# WheelDriver_RevC_newlayoutfinal.net
KiCad netlist of a schematic drawn in EAGLE
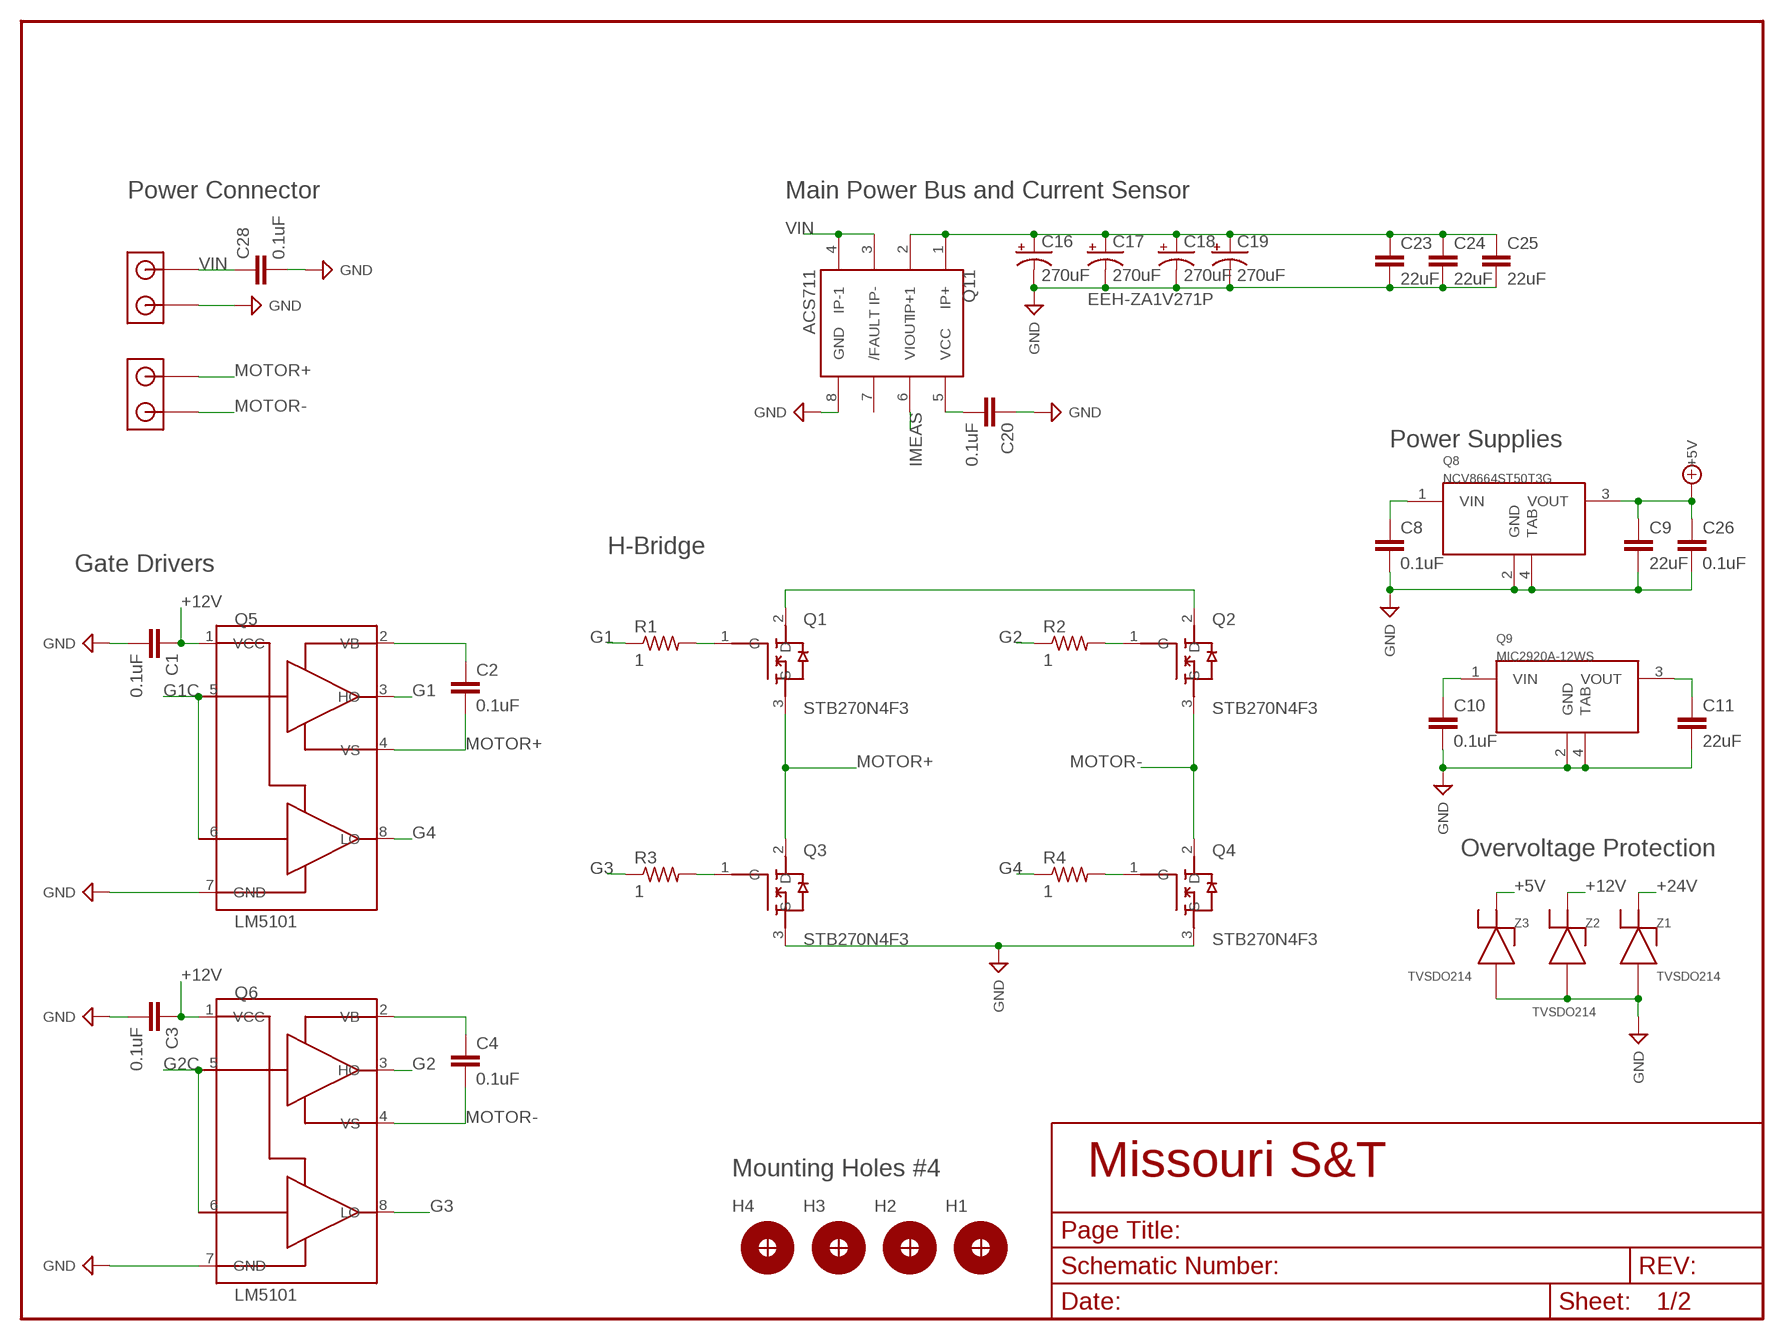
[diagram p0: schematic, sheet 1]
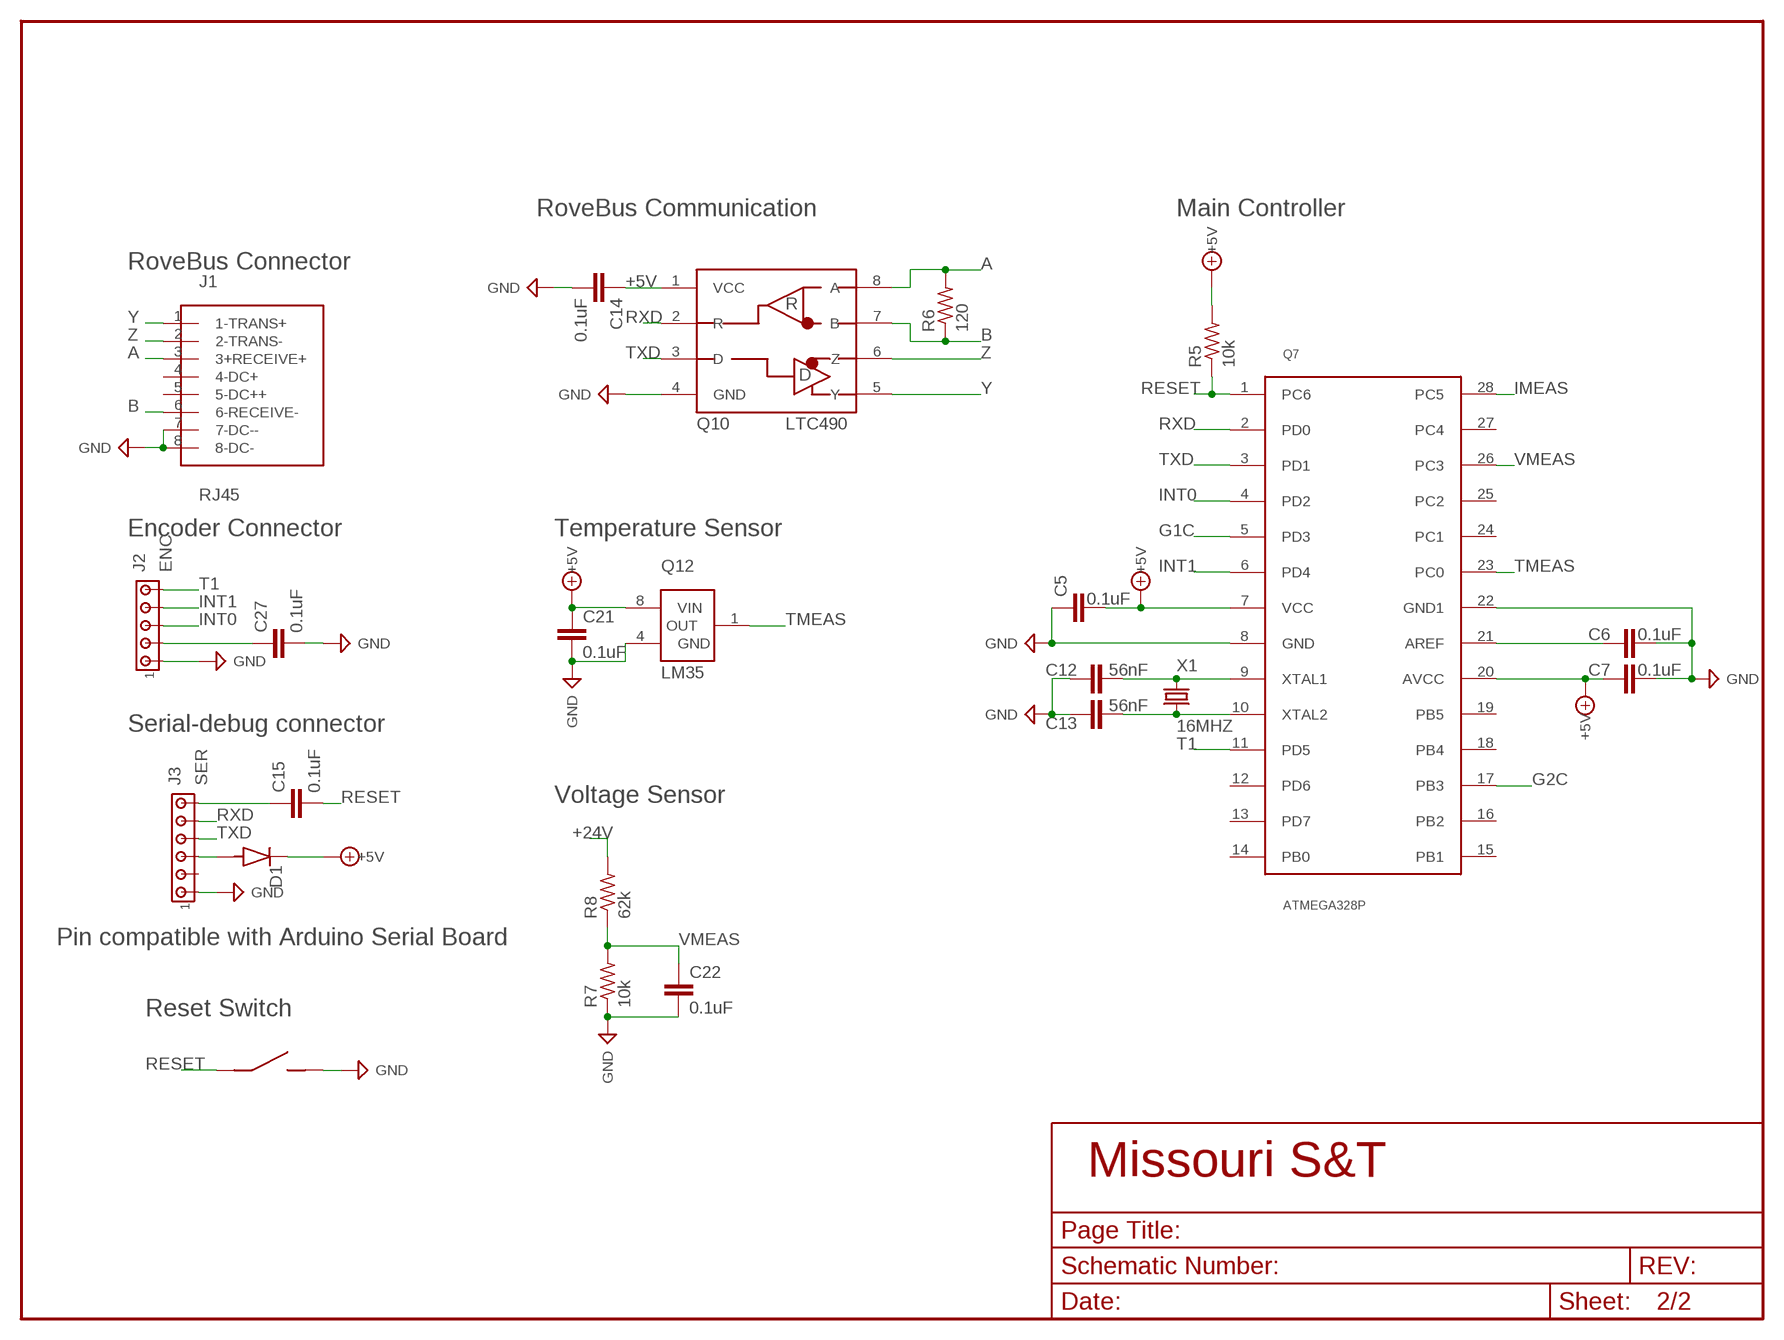
[diagram p1: schematic, sheet 2]

(export (version "E")
  (design (tool "Eeschema 10.0.6"))
  (components
    (comp (ref "C1")
      (value "0.1uF")
      (footprint "eagle-import:C_0805")
      (libsource (lib "eagle-import") (part "Master_C_CAP_0805"))
    )
    (comp (ref "C2")
      (value "0.1uF")
      (footprint "eagle-import:C_1206")
      (libsource (lib "eagle-import") (part "Master_C_CAP_1206"))
    )
    (comp (ref "C3")
      (value "0.1uF")
      (footprint "eagle-import:C_1206")
      (libsource (lib "eagle-import") (part "Master_C_CAP_1206"))
    )
    (comp (ref "C4")
      (value "0.1uF")
      (footprint "eagle-import:C_1206")
      (libsource (lib "eagle-import") (part "Master_C_CAP_1206"))
    )
    (comp (ref "C8")
      (value "0.1uF")
      (footprint "eagle-import:C_1206")
      (libsource (lib "eagle-import") (part "Master_C_CAP_1206"))
    )
    (comp (ref "C9")
      (value "22uF")
      (footprint "eagle-import:C_1206")
      (libsource (lib "eagle-import") (part "Master_C_CAP_1206"))
    )
    (comp (ref "C10")
      (value "0.1uF")
      (footprint "eagle-import:C_1206")
      (libsource (lib "eagle-import") (part "Master_C_CAP_1206"))
    )
    (comp (ref "C11")
      (value "22uF")
      (footprint "eagle-import:C_1206")
      (libsource (lib "eagle-import") (part "Master_C_CAP_1206"))
    )
    (comp (ref "C16")
      (value "270uF")
      (footprint "eagle-import:C_10MMSM")
      (libsource (lib "eagle-import") (part "CAP_POL10MMSM"))
    )
    (comp (ref "C17")
      (value "270uF")
      (footprint "eagle-import:C_10MMSM")
      (libsource (lib "eagle-import") (part "CAP_POL10MMSM"))
    )
    (comp (ref "C18")
      (value "270uF")
      (footprint "eagle-import:C_10MMSM")
      (libsource (lib "eagle-import") (part "CAP_POL10MMSM"))
    )
    (comp (ref "C19")
      (value "270uF")
      (footprint "eagle-import:C_10MMSM")
      (libsource (lib "eagle-import") (part "CAP_POL10MMSM"))
    )
    (comp (ref "C20")
      (value "0.1uF")
      (footprint "eagle-import:C_1206")
      (libsource (lib "eagle-import") (part "Master_C_CAP_1206"))
    )
    (comp (ref "C23")
      (value "22uF")
      (footprint "eagle-import:C_1206")
      (libsource (lib "eagle-import") (part "C_CAP_1206"))
    )
    (comp (ref "C24")
      (value "22uF")
      (footprint "eagle-import:C_1206")
      (libsource (lib "eagle-import") (part "C_CAP_1206"))
    )
    (comp (ref "C25")
      (value "22uF")
      (footprint "eagle-import:C_1206")
      (libsource (lib "eagle-import") (part "C_CAP_1206"))
    )
    (comp (ref "C26")
      (value "0.1uF")
      (footprint "eagle-import:C_1206")
      (libsource (lib "eagle-import") (part "Master_C_CAP_1206"))
    )
    (comp (ref "C28")
      (value "0.1uF")
      (footprint "eagle-import:C_1206")
      (libsource (lib "eagle-import") (part "Master_C_CAP_1206"))
    )
    (comp (ref "H1")
      (value "H_MNTHOLE_#4")
      (footprint "eagle-import:H_MNTHOLE_#4")
      (libsource (lib "eagle-import") (part "H_MNTHOLE_#4"))
    )
    (comp (ref "H2")
      (value "H_MNTHOLE_#4")
      (footprint "eagle-import:H_MNTHOLE_#4")
      (libsource (lib "eagle-import") (part "H_MNTHOLE_#4"))
    )
    (comp (ref "H3")
      (value "H_MNTHOLE_#4")
      (footprint "eagle-import:H_MNTHOLE_#4")
      (libsource (lib "eagle-import") (part "H_MNTHOLE_#4"))
    )
    (comp (ref "H4")
      (value "H_MNTHOLE_#4")
      (footprint "eagle-import:H_MNTHOLE_#4")
      (libsource (lib "eagle-import") (part "H_MNTHOLE_#4"))
    )
    (comp (ref "J4")
      (value "J_1546074-2")
      (footprint "eagle-import:THERM_BLOCK_2")
      (libsource (lib "eagle-import") (part "J_1546074-2"))
    )
    (comp (ref "J5")
      (value "J_1546074-2")
      (footprint "eagle-import:THERM_BLOCK_2")
      (libsource (lib "eagle-import") (part "J_1546074-2"))
    )
    (comp (ref "Q1")
      (value "STB270N4F3")
      (footprint "eagle-import:TO-263")
      (libsource (lib "eagle-import") (part "N-CH-MOSFETTO263"))
    )
    (comp (ref "Q2")
      (value "STB270N4F3")
      (footprint "eagle-import:TO-263")
      (libsource (lib "eagle-import") (part "N-CH-MOSFETTO263"))
    )
    (comp (ref "Q3")
      (value "STB270N4F3")
      (footprint "eagle-import:TO-263")
      (libsource (lib "eagle-import") (part "N-CH-MOSFETTO263"))
    )
    (comp (ref "Q4")
      (value "STB270N4F3")
      (footprint "eagle-import:TO-263")
      (libsource (lib "eagle-import") (part "N-CH-MOSFETTO263"))
    )
    (comp (ref "Q5")
      (value "LM5101")
      (footprint "eagle-import:SOIC8")
      (libsource (lib "eagle-import") (part "LM5101SOIC8"))
    )
    (comp (ref "Q6")
      (value "LM5101")
      (footprint "eagle-import:SOIC8")
      (libsource (lib "eagle-import") (part "LM5101SOIC8"))
    )
    (comp (ref "Q8")
      (value "NCV8664ST50T3G")
      (footprint "eagle-import:SOT-223")
      (libsource (lib "eagle-import") (part "LDO-4PINSOT223"))
    )
    (comp (ref "Q9")
      (value "MIC2920A-12WS")
      (footprint "eagle-import:SOT-223")
      (libsource (lib "eagle-import") (part "LDO-4PINSOT223"))
    )
    (comp (ref "Q11")
      (value "ACS711")
      (footprint "eagle-import:SOIC8")
      (libsource (lib "eagle-import") (part "ACS711SOIC"))
    )
    (comp (ref "R1")
      (value "1")
      (footprint "eagle-import:R_0805")
      (libsource (lib "eagle-import") (part "R_RES_0805"))
    )
    (comp (ref "R2")
      (value "1")
      (footprint "eagle-import:R_0805")
      (libsource (lib "eagle-import") (part "R_RES_0805"))
    )
    (comp (ref "R3")
      (value "1")
      (footprint "eagle-import:R_1206")
      (libsource (lib "eagle-import") (part "R_RES_1206"))
    )
    (comp (ref "R4")
      (value "1")
      (footprint "eagle-import:R_1206")
      (libsource (lib "eagle-import") (part "R_RES_1206"))
    )
    (comp (ref "Z1")
      (value "TVSDO214")
      (footprint "eagle-import:DO-214AC")
      (libsource (lib "eagle-import") (part "Z_TVSDO214"))
    )
    (comp (ref "Z2")
      (value "TVSDO214")
      (footprint "eagle-import:DO-214AC")
      (libsource (lib "eagle-import") (part "Z_TVSDO214"))
    )
    (comp (ref "Z3")
      (value "TVSDO214")
      (footprint "eagle-import:DO-214AC")
      (libsource (lib "eagle-import") (part "Z_TVSDO214"))
    )
    (comp (ref "C5")
      (value "0.1uF")
      (footprint "eagle-import:C_1206")
      (libsource (lib "eagle-import") (part "Master_C_CAP_1206"))
    )
    (comp (ref "C6")
      (value "0.1uF")
      (footprint "eagle-import:C_0805")
      (libsource (lib "eagle-import") (part "Master_C_CAP_0805"))
    )
    (comp (ref "C7")
      (value "0.1uF")
      (footprint "eagle-import:C_0805")
      (libsource (lib "eagle-import") (part "Master_C_CAP_0805"))
    )
    (comp (ref "C12")
      (value "56nF")
      (footprint "eagle-import:C_1206")
      (libsource (lib "eagle-import") (part "Master_C_CAP_1206"))
    )
    (comp (ref "C13")
      (value "56nF")
      (footprint "eagle-import:C_1206")
      (libsource (lib "eagle-import") (part "Master_C_CAP_1206"))
    )
    (comp (ref "C14")
      (value "0.1uF")
      (footprint "eagle-import:C_1206")
      (libsource (lib "eagle-import") (part "Master_C_CAP_1206"))
    )
    (comp (ref "C15")
      (value "0.1uF")
      (footprint "eagle-import:C_0805")
      (libsource (lib "eagle-import") (part "Master_C_CAP_0805"))
    )
    (comp (ref "C21")
      (value "0.1uF")
      (footprint "eagle-import:C_0805")
      (libsource (lib "eagle-import") (part "Master_C_CAP_0805"))
    )
    (comp (ref "C22")
      (value "0.1uF")
      (footprint "eagle-import:C_0805")
      (libsource (lib "eagle-import") (part "Master_C_CAP_0805"))
    )
    (comp (ref "C27")
      (value "0.1uF")
      (footprint "eagle-import:C_1206")
      (libsource (lib "eagle-import") (part "Master_C_CAP_1206"))
    )
    (comp (ref "D1")
      (value "D_DIODEDO214AC")
      (footprint "eagle-import:DO-214AC")
      (libsource (lib "eagle-import") (part "D_DIODEDO214AC"))
    )
    (comp (ref "J1")
      (value "RJ45")
      (footprint "eagle-import:RJ45-CAT5E")
      (libsource (lib "eagle-import") (part "RJ45"))
    )
    (comp (ref "J2")
      (value "ENC")
      (footprint "eagle-import:J_MTA100_5P")
      (libsource (lib "eagle-import") (part "J_MTA5P_100"))
    )
    (comp (ref "J3")
      (value "SER")
      (footprint "eagle-import:J_MTA100_6P")
      (libsource (lib "eagle-import") (part "J_MTA6P_100"))
    )
    (comp (ref "J6")
      (value "J_MC32857")
      (footprint "eagle-import:J_TOGGLE")
      (libsource (lib "eagle-import") (part "J_MC32857"))
    )
    (comp (ref "Q7")
      (value "ATMEGA328P")
      (footprint "eagle-import:DIP28")
      (libsource (lib "eagle-import") (part "Q_ATMEGA328P"))
    )
    (comp (ref "Q10")
      (value "LTC490")
      (footprint "eagle-import:SOIC8")
      (libsource (lib "eagle-import") (part "RS485FULL"))
    )
    (comp (ref "Q12")
      (value "LM35")
      (footprint "eagle-import:SOIC8")
      (libsource (lib "eagle-import") (part "Q_LM35SOIC8"))
    )
    (comp (ref "R5")
      (value "10k")
      (footprint "eagle-import:R_0805")
      (libsource (lib "eagle-import") (part "R_RES_0805"))
    )
    (comp (ref "R6")
      (value "120")
      (footprint "eagle-import:R_0805")
      (libsource (lib "eagle-import") (part "R_RES_0805"))
    )
    (comp (ref "R7")
      (value "10k")
      (footprint "eagle-import:R_0805")
      (libsource (lib "eagle-import") (part "R_RES_0805"))
    )
    (comp (ref "R8")
      (value "62k")
      (footprint "eagle-import:R_0805")
      (libsource (lib "eagle-import") (part "R_RES_0805"))
    )
    (comp (ref "X1")
      (value "16MHZ")
      (footprint "eagle-import:HC-49")
      (libsource (lib "eagle-import") (part "X_HC49SCRYSTALTH"))
    )
  )
  (nets
    (net (code "1") (name "+5V") (class "Default")
      (node (ref "C14") (pin "1") (pinfunction "1_1") (pintype "passive"))
      (node (ref "C21") (pin "1") (pinfunction "1_1") (pintype "passive"))
      (node (ref "C26") (pin "1") (pinfunction "1_1") (pintype "passive"))
      (node (ref "C27") (pin "1") (pinfunction "1_1") (pintype "passive"))
      (node (ref "C5") (pin "2") (pinfunction "2_2") (pintype "passive"))
      (node (ref "C7") (pin "1") (pinfunction "1_1") (pintype "passive"))
      (node (ref "C9") (pin "1") (pinfunction "1_1") (pintype "passive"))
      (node (ref "D1") (pin "C") (pinfunction "C_C") (pintype "bidirectional"))
      (node (ref "J2") (pin "2") (pinfunction "2_2") (pintype "passive"))
      (node (ref "Q10") (pin "1") (pinfunction "VCC_1") (pintype "bidirectional"))
      (node (ref "Q12") (pin "8") (pinfunction "VIN_8") (pintype "bidirectional"))
      (node (ref "Q7") (pin "20") (pinfunction "AVCC_20") (pintype "bidirectional"))
      (node (ref "Q7") (pin "7") (pinfunction "VCC_7") (pintype "bidirectional"))
      (node (ref "Q8") (pin "3") (pinfunction "VOUT_3") (pintype "bidirectional"))
      (node (ref "R5") (pin "2") (pinfunction "2_2") (pintype "passive"))
      (node (ref "Z3") (pin "C") (pinfunction "C_C") (pintype "bidirectional"))
    )
    (net (code "2") (name "+12V") (class "Default")
      (node (ref "C1") (pin "1") (pinfunction "1_1") (pintype "passive"))
      (node (ref "C11") (pin "1") (pinfunction "1_1") (pintype "passive"))
      (node (ref "C3") (pin "1") (pinfunction "1_1") (pintype "passive"))
      (node (ref "Q5") (pin "1") (pinfunction "VCC_1") (pintype "bidirectional"))
      (node (ref "Q6") (pin "1") (pinfunction "VCC_1") (pintype "bidirectional"))
      (node (ref "Q9") (pin "3") (pinfunction "VOUT_3") (pintype "bidirectional"))
      (node (ref "Z2") (pin "C") (pinfunction "C_C") (pintype "bidirectional"))
    )
    (net (code "3") (name "+24V") (class "Default")
      (node (ref "C10") (pin "1") (pinfunction "1_1") (pintype "passive"))
      (node (ref "C16") (pin "+") (pinfunction "+_+") (pintype "passive"))
      (node (ref "C17") (pin "+") (pinfunction "+_+") (pintype "passive"))
      (node (ref "C18") (pin "+") (pinfunction "+_+") (pintype "passive"))
      (node (ref "C19") (pin "+") (pinfunction "+_+") (pintype "passive"))
      (node (ref "C23") (pin "1") (pinfunction "1_1") (pintype "passive"))
      (node (ref "C24") (pin "1") (pinfunction "1_1") (pintype "passive"))
      (node (ref "C25") (pin "1") (pinfunction "1_1") (pintype "passive"))
      (node (ref "Q1") (pin "2") (pinfunction "D_2") (pintype "bidirectional"))
      (node (ref "Q11") (pin "1") (pinfunction "IP+_1") (pintype "bidirectional"))
      (node (ref "Q11") (pin "2") (pinfunction "IP+1_2") (pintype "bidirectional"))
      (node (ref "Q2") (pin "2") (pinfunction "D_2") (pintype "bidirectional"))
      (node (ref "Q9") (pin "1") (pinfunction "VIN_1") (pintype "bidirectional"))
      (node (ref "R8") (pin "2") (pinfunction "2_2") (pintype "passive"))
      (node (ref "Z1") (pin "C") (pinfunction "C_C") (pintype "bidirectional"))
    )
    (net (code "4") (name "A") (class "Default")
      (node (ref "J1") (pin "3") (pinfunction "3+RECEIVE+_3") (pintype "bidirectional"))
      (node (ref "Q10") (pin "8") (pinfunction "A_8") (pintype "bidirectional"))
      (node (ref "R6") (pin "2") (pinfunction "2_2") (pintype "passive"))
    )
    (net (code "5") (name "B") (class "Default")
      (node (ref "J1") (pin "6") (pinfunction "6-RECEIVE-_6") (pintype "bidirectional"))
      (node (ref "Q10") (pin "7") (pinfunction "B_7") (pintype "bidirectional"))
      (node (ref "R6") (pin "1") (pinfunction "1_1") (pintype "passive"))
    )
    (net (code "6") (name "G1") (class "Default")
      (node (ref "Q5") (pin "3") (pinfunction "HO_3") (pintype "bidirectional"))
      (node (ref "R1") (pin "1") (pinfunction "1_1") (pintype "passive"))
    )
    (net (code "7") (name "G1C") (class "Default")
      (node (ref "Q5") (pin "5") (pinfunction "HI_5") (pintype "bidirectional"))
      (node (ref "Q5") (pin "6") (pinfunction "LI_6") (pintype "bidirectional"))
      (node (ref "Q7") (pin "5") (pinfunction "PD3_5") (pintype "bidirectional"))
    )
    (net (code "8") (name "G2") (class "Default")
      (node (ref "Q6") (pin "3") (pinfunction "HO_3") (pintype "bidirectional"))
      (node (ref "R2") (pin "1") (pinfunction "1_1") (pintype "passive"))
    )
    (net (code "9") (name "G2C") (class "Default")
      (node (ref "Q6") (pin "5") (pinfunction "HI_5") (pintype "bidirectional"))
      (node (ref "Q6") (pin "6") (pinfunction "LI_6") (pintype "bidirectional"))
      (node (ref "Q7") (pin "17") (pinfunction "PB3_17") (pintype "bidirectional"))
    )
    (net (code "10") (name "G3") (class "Default")
      (node (ref "Q6") (pin "8") (pinfunction "LO_8") (pintype "bidirectional"))
      (node (ref "R3") (pin "1") (pinfunction "1_1") (pintype "passive"))
    )
    (net (code "11") (name "G4") (class "Default")
      (node (ref "Q5") (pin "8") (pinfunction "LO_8") (pintype "bidirectional"))
      (node (ref "R4") (pin "1") (pinfunction "1_1") (pintype "passive"))
    )
    (net (code "12") (name "GND") (class "Default")
      (node (ref "C1") (pin "2") (pinfunction "2_2") (pintype "passive"))
      (node (ref "C10") (pin "2") (pinfunction "2_2") (pintype "passive"))
      (node (ref "C11") (pin "2") (pinfunction "2_2") (pintype "passive"))
      (node (ref "C12") (pin "1") (pinfunction "1_1") (pintype "passive"))
      (node (ref "C13") (pin "1") (pinfunction "1_1") (pintype "passive"))
      (node (ref "C14") (pin "2") (pinfunction "2_2") (pintype "passive"))
      (node (ref "C16") (pin "-") (pinfunction "-_-") (pintype "passive"))
      (node (ref "C17") (pin "-") (pinfunction "-_-") (pintype "passive"))
      (node (ref "C18") (pin "-") (pinfunction "-_-") (pintype "passive"))
      (node (ref "C19") (pin "-") (pinfunction "-_-") (pintype "passive"))
      (node (ref "C20") (pin "1") (pinfunction "1_1") (pintype "passive"))
      (node (ref "C21") (pin "2") (pinfunction "2_2") (pintype "passive"))
      (node (ref "C22") (pin "2") (pinfunction "2_2") (pintype "passive"))
      (node (ref "C23") (pin "2") (pinfunction "2_2") (pintype "passive"))
      (node (ref "C24") (pin "2") (pinfunction "2_2") (pintype "passive"))
      (node (ref "C25") (pin "2") (pinfunction "2_2") (pintype "passive"))
      (node (ref "C26") (pin "2") (pinfunction "2_2") (pintype "passive"))
      (node (ref "C27") (pin "2") (pinfunction "2_2") (pintype "passive"))
      (node (ref "C28") (pin "2") (pinfunction "2_2") (pintype "passive"))
      (node (ref "C3") (pin "2") (pinfunction "2_2") (pintype "passive"))
      (node (ref "C5") (pin "1") (pinfunction "1_1") (pintype "passive"))
      (node (ref "C6") (pin "2") (pinfunction "2_2") (pintype "passive"))
      (node (ref "C7") (pin "2") (pinfunction "2_2") (pintype "passive"))
      (node (ref "C8") (pin "2") (pinfunction "2_2") (pintype "passive"))
      (node (ref "C9") (pin "2") (pinfunction "2_2") (pintype "passive"))
      (node (ref "J1") (pin "7") (pinfunction "7-DC--_7") (pintype "bidirectional"))
      (node (ref "J1") (pin "8") (pinfunction "8-DC-_8") (pintype "bidirectional"))
      (node (ref "J2") (pin "1") (pinfunction "1_1") (pintype "passive"))
      (node (ref "J3") (pin "1") (pinfunction "1_1") (pintype "passive"))
      (node (ref "J4") (pin "P$1") (pinfunction "P$1_P$1") (pintype "bidirectional"))
      (node (ref "J6") (pin "P$2") (pinfunction "2_P$2") (pintype "bidirectional"))
      (node (ref "Q10") (pin "4") (pinfunction "GND_4") (pintype "bidirectional"))
      (node (ref "Q11") (pin "8") (pinfunction "GND_8") (pintype "bidirectional"))
      (node (ref "Q12") (pin "4") (pinfunction "GND_4") (pintype "bidirectional"))
      (node (ref "Q3") (pin "3") (pinfunction "S_3") (pintype "bidirectional"))
      (node (ref "Q4") (pin "3") (pinfunction "S_3") (pintype "bidirectional"))
      (node (ref "Q5") (pin "7") (pinfunction "GND_7") (pintype "bidirectional"))
      (node (ref "Q6") (pin "7") (pinfunction "GND_7") (pintype "bidirectional"))
      (node (ref "Q7") (pin "22") (pinfunction "GND1_22") (pintype "bidirectional"))
      (node (ref "Q7") (pin "8") (pinfunction "GND_8") (pintype "bidirectional"))
      (node (ref "Q8") (pin "2") (pinfunction "GND_2") (pintype "bidirectional"))
      (node (ref "Q8") (pin "4") (pinfunction "TAB_4") (pintype "bidirectional"))
      (node (ref "Q9") (pin "2") (pinfunction "GND_2") (pintype "bidirectional"))
      (node (ref "Q9") (pin "4") (pinfunction "TAB_4") (pintype "bidirectional"))
      (node (ref "R7") (pin "1") (pinfunction "1_1") (pintype "passive"))
      (node (ref "Z1") (pin "A") (pinfunction "A_A") (pintype "bidirectional"))
      (node (ref "Z2") (pin "A") (pinfunction "A_A") (pintype "bidirectional"))
      (node (ref "Z3") (pin "A") (pinfunction "A_A") (pintype "bidirectional"))
    )
    (net (code "13") (name "IMEAS") (class "Default")
      (node (ref "Q11") (pin "6") (pinfunction "VIOUT_6") (pintype "bidirectional"))
      (node (ref "Q7") (pin "28") (pinfunction "PC5_28") (pintype "bidirectional"))
    )
    (net (code "14") (name "INT0") (class "Default")
      (node (ref "J2") (pin "3") (pinfunction "3_3") (pintype "passive"))
      (node (ref "Q7") (pin "4") (pinfunction "PD2_4") (pintype "bidirectional"))
    )
    (net (code "15") (name "INT1") (class "Default")
      (node (ref "J2") (pin "4") (pinfunction "4_4") (pintype "passive"))
      (node (ref "Q7") (pin "6") (pinfunction "PD4_6") (pintype "bidirectional"))
    )
    (net (code "16") (name "MOTOR+") (class "Default")
      (node (ref "C2") (pin "2") (pinfunction "2_2") (pintype "passive"))
      (node (ref "J5") (pin "P$2") (pinfunction "P$2_P$2") (pintype "bidirectional"))
      (node (ref "Q1") (pin "3") (pinfunction "S_3") (pintype "bidirectional"))
      (node (ref "Q3") (pin "2") (pinfunction "D_2") (pintype "bidirectional"))
      (node (ref "Q5") (pin "4") (pinfunction "VS_4") (pintype "bidirectional"))
    )
    (net (code "17") (name "MOTOR-") (class "Default")
      (node (ref "C4") (pin "2") (pinfunction "2_2") (pintype "passive"))
      (node (ref "J5") (pin "P$1") (pinfunction "P$1_P$1") (pintype "bidirectional"))
      (node (ref "Q2") (pin "3") (pinfunction "S_3") (pintype "bidirectional"))
      (node (ref "Q4") (pin "2") (pinfunction "D_2") (pintype "bidirectional"))
      (node (ref "Q6") (pin "4") (pinfunction "VS_4") (pintype "bidirectional"))
    )
    (net (code "18") (name "Net-(C15-Pad1)") (class "Default")
      (node (ref "C15") (pin "1") (pinfunction "1_1") (pintype "passive"))
      (node (ref "J3") (pin "6") (pinfunction "6_6") (pintype "passive"))
    )
    (net (code "19") (name "Net-(D1-PadA)") (class "Default")
      (node (ref "D1") (pin "A") (pinfunction "A_A") (pintype "bidirectional"))
      (node (ref "J3") (pin "3") (pinfunction "3_3") (pintype "passive"))
    )
    (net (code "20") (name "Net-(Q1-G)") (class "Default")
      (node (ref "Q1") (pin "1") (pinfunction "G_1") (pintype "bidirectional"))
      (node (ref "R1") (pin "2") (pinfunction "2_2") (pintype "passive"))
    )
    (net (code "21") (name "Net-(Q2-G)") (class "Default")
      (node (ref "Q2") (pin "1") (pinfunction "G_1") (pintype "bidirectional"))
      (node (ref "R2") (pin "2") (pinfunction "2_2") (pintype "passive"))
    )
    (net (code "22") (name "Net-(Q3-G)") (class "Default")
      (node (ref "Q3") (pin "1") (pinfunction "G_1") (pintype "bidirectional"))
      (node (ref "R3") (pin "2") (pinfunction "2_2") (pintype "passive"))
    )
    (net (code "23") (name "Net-(Q4-G)") (class "Default")
      (node (ref "Q4") (pin "1") (pinfunction "G_1") (pintype "bidirectional"))
      (node (ref "R4") (pin "2") (pinfunction "2_2") (pintype "passive"))
    )
    (net (code "24") (name "Net-(Q5-VB)") (class "Default")
      (node (ref "C2") (pin "1") (pinfunction "1_1") (pintype "passive"))
      (node (ref "Q5") (pin "2") (pinfunction "VB_2") (pintype "bidirectional"))
    )
    (net (code "25") (name "Net-(Q6-VB)") (class "Default")
      (node (ref "C4") (pin "1") (pinfunction "1_1") (pintype "passive"))
      (node (ref "Q6") (pin "2") (pinfunction "VB_2") (pintype "bidirectional"))
    )
    (net (code "26") (name "Net-(Q7-AREF)") (class "Default")
      (node (ref "C6") (pin "1") (pinfunction "1_1") (pintype "passive"))
      (node (ref "Q7") (pin "21") (pinfunction "AREF_21") (pintype "bidirectional"))
    )
    (net (code "27") (name "Net-(Q7-XTAL1)") (class "Default")
      (node (ref "C12") (pin "2") (pinfunction "2_2") (pintype "passive"))
      (node (ref "Q7") (pin "9") (pinfunction "XTAL1_9") (pintype "bidirectional"))
      (node (ref "X1") (pin "P$1") (pinfunction "1_P$1") (pintype "passive"))
    )
    (net (code "28") (name "Net-(Q7-XTAL2)") (class "Default")
      (node (ref "C13") (pin "2") (pinfunction "2_2") (pintype "passive"))
      (node (ref "Q7") (pin "10") (pinfunction "XTAL2_10") (pintype "bidirectional"))
      (node (ref "X1") (pin "P$2") (pinfunction "2_P$2") (pintype "passive"))
    )
    (net (code "29") (name "Net-(Q11-VCC)") (class "Default")
      (node (ref "C20") (pin "2") (pinfunction "2_2") (pintype "passive"))
      (node (ref "Q11") (pin "5") (pinfunction "VCC_5") (pintype "bidirectional"))
    )
    (net (code "30") (name "RESET") (class "Default")
      (node (ref "C15") (pin "2") (pinfunction "2_2") (pintype "passive"))
      (node (ref "J6") (pin "P$1") (pinfunction "1_P$1") (pintype "bidirectional"))
      (node (ref "Q7") (pin "1") (pinfunction "PC6_1") (pintype "bidirectional"))
      (node (ref "R5") (pin "1") (pinfunction "1_1") (pintype "passive"))
    )
    (net (code "31") (name "RXD") (class "Default")
      (node (ref "J3") (pin "5") (pinfunction "5_5") (pintype "passive"))
      (node (ref "Q10") (pin "2") (pinfunction "R_2") (pintype "bidirectional"))
      (node (ref "Q7") (pin "2") (pinfunction "PD0_2") (pintype "bidirectional"))
    )
    (net (code "32") (name "T1") (class "Default")
      (node (ref "J2") (pin "5") (pinfunction "5_5") (pintype "passive"))
      (node (ref "Q7") (pin "11") (pinfunction "PD5_11") (pintype "bidirectional"))
    )
    (net (code "33") (name "TMEAS") (class "Default")
      (node (ref "Q12") (pin "1") (pinfunction "OUT_1") (pintype "bidirectional"))
      (node (ref "Q7") (pin "23") (pinfunction "PC0_23") (pintype "bidirectional"))
    )
    (net (code "34") (name "TXD") (class "Default")
      (node (ref "J3") (pin "4") (pinfunction "4_4") (pintype "passive"))
      (node (ref "Q10") (pin "3") (pinfunction "D_3") (pintype "bidirectional"))
      (node (ref "Q7") (pin "3") (pinfunction "PD1_3") (pintype "bidirectional"))
    )
    (net (code "35") (name "VIN") (class "Default")
      (node (ref "C28") (pin "1") (pinfunction "1_1") (pintype "passive"))
      (node (ref "C8") (pin "1") (pinfunction "1_1") (pintype "passive"))
      (node (ref "J4") (pin "P$2") (pinfunction "P$2_P$2") (pintype "bidirectional"))
      (node (ref "Q11") (pin "3") (pinfunction "IP-_3") (pintype "bidirectional"))
      (node (ref "Q11") (pin "4") (pinfunction "IP-1_4") (pintype "bidirectional"))
      (node (ref "Q8") (pin "1") (pinfunction "VIN_1") (pintype "bidirectional"))
    )
    (net (code "36") (name "VMEAS") (class "Default")
      (node (ref "C22") (pin "1") (pinfunction "1_1") (pintype "passive"))
      (node (ref "Q7") (pin "26") (pinfunction "PC3_26") (pintype "bidirectional"))
      (node (ref "R7") (pin "2") (pinfunction "2_2") (pintype "passive"))
      (node (ref "R8") (pin "1") (pinfunction "1_1") (pintype "passive"))
    )
    (net (code "37") (name "Y") (class "Default")
      (node (ref "J1") (pin "1") (pinfunction "1-TRANS+_1") (pintype "bidirectional"))
      (node (ref "Q10") (pin "5") (pinfunction "Y_5") (pintype "bidirectional"))
    )
    (net (code "38") (name "Z") (class "Default")
      (node (ref "J1") (pin "2") (pinfunction "2-TRANS-_2") (pintype "bidirectional"))
      (node (ref "Q10") (pin "6") (pinfunction "Z_6") (pintype "bidirectional"))
    )
    (net (code "39") (name "unconnected-(H1-Pad1)") (class "Default")
      (node (ref "H1") (pin "1") (pinfunction "1_1") (pintype "passive"))
    )
    (net (code "40") (name "unconnected-(H2-Pad1)") (class "Default")
      (node (ref "H2") (pin "1") (pinfunction "1_1") (pintype "passive"))
    )
    (net (code "41") (name "unconnected-(H3-Pad1)") (class "Default")
      (node (ref "H3") (pin "1") (pinfunction "1_1") (pintype "passive"))
    )
    (net (code "42") (name "unconnected-(H4-Pad1)") (class "Default")
      (node (ref "H4") (pin "1") (pinfunction "1_1") (pintype "passive"))
    )
    (net (code "43") (name "unconnected-(J1-4-DC+-Pad4)") (class "Default")
      (node (ref "J1") (pin "4") (pinfunction "4-DC+_4") (pintype "bidirectional"))
    )
    (net (code "44") (name "unconnected-(J1-5-DC++-Pad5)") (class "Default")
      (node (ref "J1") (pin "5") (pinfunction "5-DC++_5") (pintype "bidirectional"))
    )
    (net (code "45") (name "unconnected-(J3-Pad2)") (class "Default")
      (node (ref "J3") (pin "2") (pinfunction "2_2") (pintype "passive"))
    )
    (net (code "46") (name "unconnected-(Q7-PB0-Pad14)") (class "Default")
      (node (ref "Q7") (pin "14") (pinfunction "PB0_14") (pintype "bidirectional"))
    )
    (net (code "47") (name "unconnected-(Q7-PB1-Pad15)") (class "Default")
      (node (ref "Q7") (pin "15") (pinfunction "PB1_15") (pintype "bidirectional"))
    )
    (net (code "48") (name "unconnected-(Q7-PB2-Pad16)") (class "Default")
      (node (ref "Q7") (pin "16") (pinfunction "PB2_16") (pintype "bidirectional"))
    )
    (net (code "49") (name "unconnected-(Q7-PB4-Pad18)") (class "Default")
      (node (ref "Q7") (pin "18") (pinfunction "PB4_18") (pintype "bidirectional"))
    )
    (net (code "50") (name "unconnected-(Q7-PB5-Pad19)") (class "Default")
      (node (ref "Q7") (pin "19") (pinfunction "PB5_19") (pintype "bidirectional"))
    )
    (net (code "51") (name "unconnected-(Q7-PC1-Pad24)") (class "Default")
      (node (ref "Q7") (pin "24") (pinfunction "PC1_24") (pintype "bidirectional"))
    )
    (net (code "52") (name "unconnected-(Q7-PC2-Pad25)") (class "Default")
      (node (ref "Q7") (pin "25") (pinfunction "PC2_25") (pintype "bidirectional"))
    )
    (net (code "53") (name "unconnected-(Q7-PC4-Pad27)") (class "Default")
      (node (ref "Q7") (pin "27") (pinfunction "PC4_27") (pintype "bidirectional"))
    )
    (net (code "54") (name "unconnected-(Q7-PD6-Pad12)") (class "Default")
      (node (ref "Q7") (pin "12") (pinfunction "PD6_12") (pintype "bidirectional"))
    )
    (net (code "55") (name "unconnected-(Q7-PD7-Pad13)") (class "Default")
      (node (ref "Q7") (pin "13") (pinfunction "PD7_13") (pintype "bidirectional"))
    )
    (net (code "56") (name "unconnected-(Q11-{slash}FAULT-Pad7)") (class "Default")
      (node (ref "Q11") (pin "7") (pinfunction "/FAULT_7") (pintype "bidirectional"))
    )
  )
)
